# lna.net
KiCad netlist of a schematic drawn in EAGLE
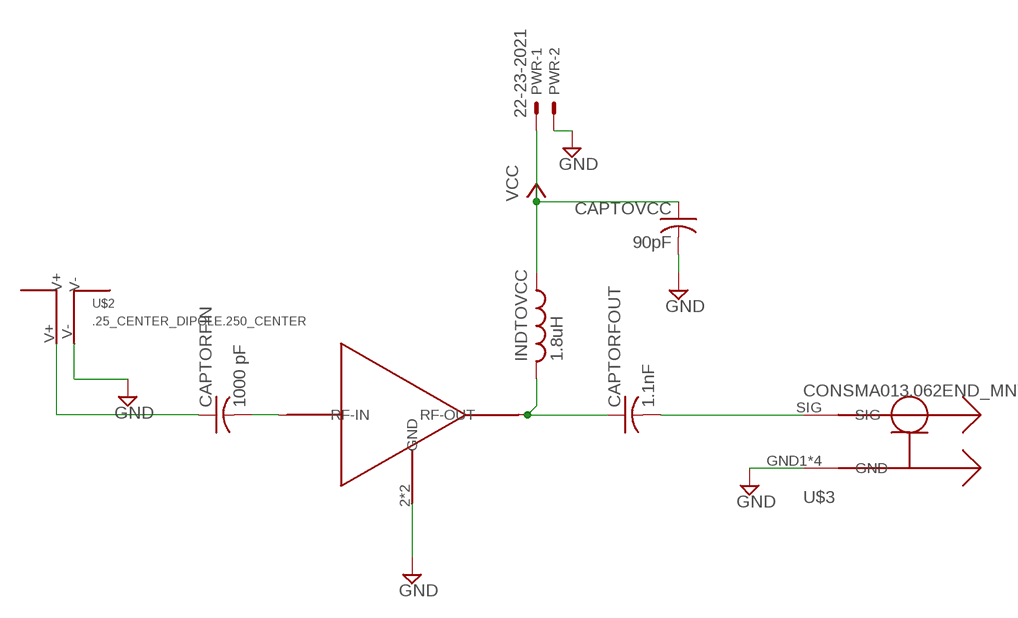
[diagram p0: schematic, sheet 1]

(export (version "E")
  (design (tool "Eeschema 10.0.6"))
  (components
    (comp (ref "CAPTORFIN")
      (value "1000 pF")
      (footprint "eagle-import:C0603")
      (libsource (lib "eagle-import") (part "C-USC0603"))
    )
    (comp (ref "CAPTORFOUT")
      (value "1.1nF")
      (footprint "eagle-import:C0603")
      (libsource (lib "eagle-import") (part "C-USC0603"))
    )
    (comp (ref "CAPTOVCC")
      (value "90pF")
      (footprint "eagle-import:C0603")
      (libsource (lib "eagle-import") (part "C-USC0603"))
    )
    (comp (ref "INDTOVCC")
      (value "1.8uH")
      (footprint "eagle-import:L2012C")
      (libsource (lib "eagle-import") (part "L-USL2012C"))
    )
    (comp (ref "PWR")
      (value "22-23-2021")
      (footprint "eagle-import:22-23-2021")
      (fields (field (name "MF") "MOLEX"))
      (libsource (lib "eagle-import") (part "22-23-2021"))
    )
    (comp (ref "U$1")
      (value "PSA4-5043+")
      (footprint "eagle-import:PSA4-5043+")
      (fields (field (name "MF") "Mini-Circuits"))
      (libsource (lib "eagle-import") (part "PSA4-5043+"))
    )
    (comp (ref "U$2")
      (value ".25_CENTER_DIPOLE.250_CENTER")
      (footprint "eagle-import:.25_SPACING")
      (libsource (lib "eagle-import") (part ".25_CENTER_DIPOLE.250_CENTER"))
    )
    (comp (ref "U$3")
      (value "CONSMA013.062END_MNT")
      (footprint "eagle-import:SMA_EDGE_MNT")
      (libsource (lib "eagle-import") (part "CONSMA013.062END_MNT"))
    )
  )
  (nets
    (net (code "1") (name "GND") (class "Default")
      (node (ref "CAPTOVCC") (pin "2") (pinfunction "2_2") (pintype "passive"))
      (node (ref "PWR") (pin "2") (pinfunction "S_2") (pintype "passive"))
      (node (ref "U$1") (pin "2") (pinfunction "GND_2") (pintype "bidirectional"))
      (node (ref "U$1") (pin "4") (pinfunction "GND_4") (pintype "bidirectional"))
      (node (ref "U$2") (pin "V-") (pinfunction "V-_V-") (pintype "bidirectional"))
      (node (ref "U$3") (pin "GND1") (pinfunction "GND_GND1") (pintype "bidirectional"))
      (node (ref "U$3") (pin "GND2") (pinfunction "GND_GND2") (pintype "bidirectional"))
      (node (ref "U$3") (pin "GND3") (pinfunction "GND_GND3") (pintype "bidirectional"))
      (node (ref "U$3") (pin "GND4") (pinfunction "GND_GND4") (pintype "bidirectional"))
    )
    (net (code "2") (name "Net-(CAPTORFIN-Pad1)") (class "Default")
      (node (ref "CAPTORFIN") (pin "1") (pinfunction "1_1") (pintype "passive"))
      (node (ref "U$2") (pin "V+") (pinfunction "V+_V+") (pintype "bidirectional"))
    )
    (net (code "3") (name "Net-(CAPTORFOUT-Pad2)") (class "Default")
      (node (ref "CAPTORFOUT") (pin "2") (pinfunction "2_2") (pintype "passive"))
      (node (ref "U$3") (pin "SIG") (pinfunction "SIG_SIG") (pintype "bidirectional"))
    )
    (net (code "4") (name "Net-(U$1-RF-IN)") (class "Default")
      (node (ref "CAPTORFIN") (pin "2") (pinfunction "2_2") (pintype "passive"))
      (node (ref "U$1") (pin "3") (pinfunction "RF-IN_3") (pintype "bidirectional"))
    )
    (net (code "5") (name "Net-(U$1-RF-OUT)") (class "Default")
      (node (ref "CAPTORFOUT") (pin "1") (pinfunction "1_1") (pintype "passive"))
      (node (ref "INDTOVCC") (pin "2") (pinfunction "2_2") (pintype "passive"))
      (node (ref "U$1") (pin "1") (pinfunction "RF-OUT_1") (pintype "bidirectional"))
    )
    (net (code "6") (name "VCC") (class "Default")
      (node (ref "CAPTOVCC") (pin "1") (pinfunction "1_1") (pintype "passive"))
      (node (ref "INDTOVCC") (pin "1") (pinfunction "1_1") (pintype "passive"))
      (node (ref "PWR") (pin "1") (pinfunction "S_1") (pintype "passive"))
    )
  )
)
